# Robo.net
KiCad netlist of a schematic drawn in Altium Designer
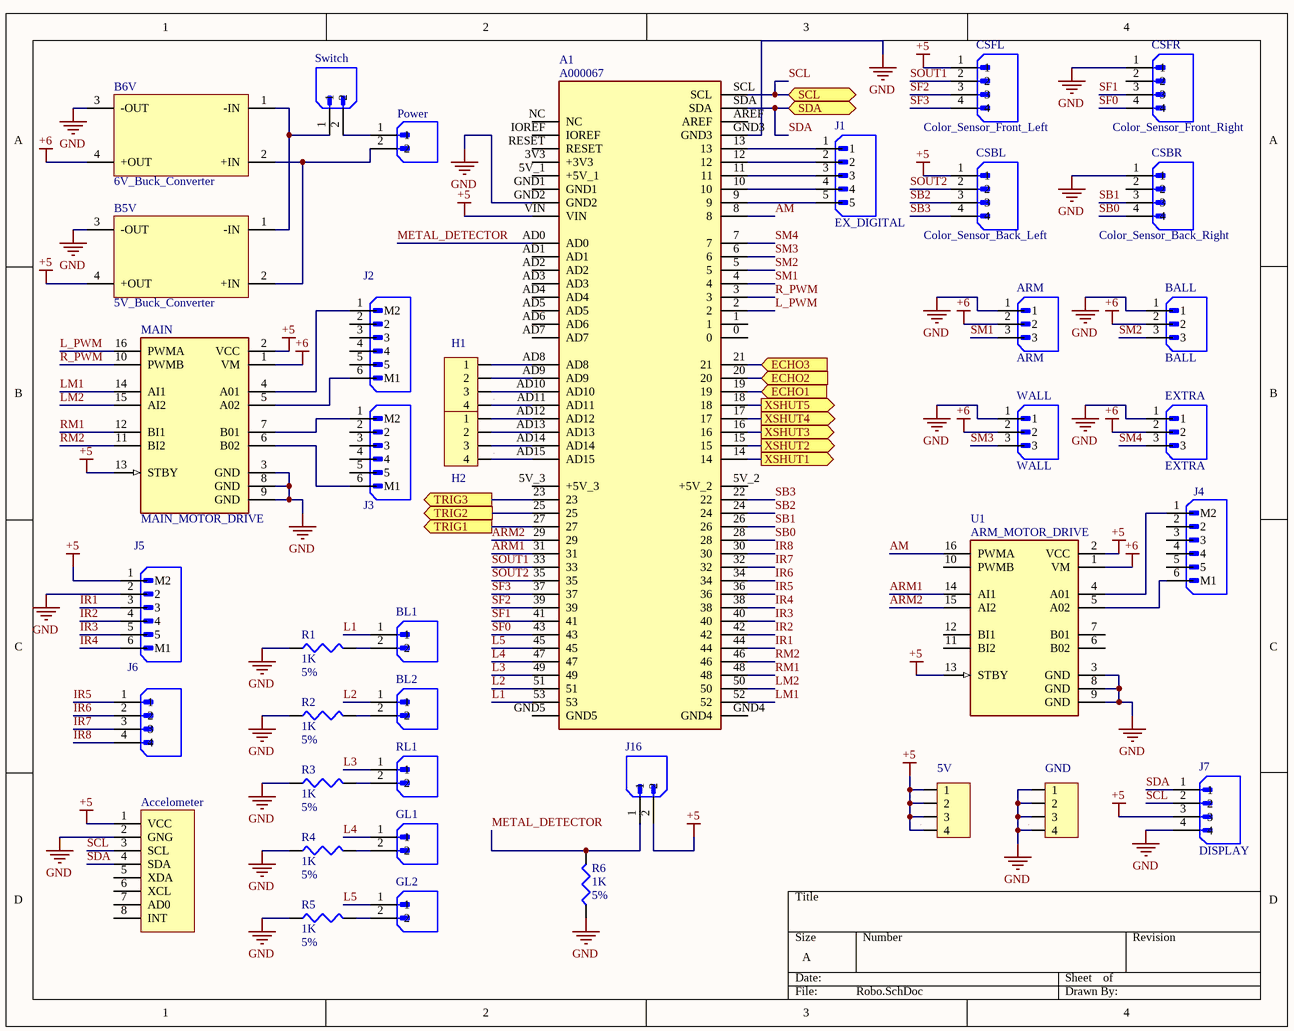
[diagram p0: Robo.SchDoc]

(export (version "E")
  (design (tool "Eeschema 10.0.6"))
  (components
    (comp (ref "5V")
      (value "61300411121")
      (footprint "61300411121 - duplicate - duplicate")
      (fields (field (name "MANUFACTURER") "Wurth Electronics"))
      (libsource (lib "") (part "61300411121_1"))
    )
    (comp (ref "A1")
      (value "A000067")
      (footprint "ARDUINO_A000067")
      (fields (field (name "MF") "Arduino"))
      (libsource (lib "robo") (part "A000067"))
    )
    (comp (ref "Accelometer")
      (value "Accelometer")
      (footprint "8pin_header")
      (libsource (lib "robo") (part "8pin_headers"))
    )
    (comp (ref "ARM")
      (value "ARM")
      (footprint "JST_B3B-XH-A (LF)(SN)")
      (description "Connector Header Through Hole 3 position 0.098 (2.50mm)")
      (fields (field (name "MF") "JST Sales America Inc.") (field (name "MP") "B3B-XH-A (LF)(SN)"))
      (libsource (lib "robo") (part "B3B-XH-A_(LF)(SN)"))
    )
    (comp (ref "B5V")
      (value "5V_Buck_Converter")
      (footprint "Buck_Conveter")
      (libsource (lib "robo") (part "Buck_Converter"))
    )
    (comp (ref "B6V")
      (value "6V_Buck_Converter")
      (footprint "Buck_Conveter")
      (libsource (lib "robo") (part "Buck_Converter"))
    )
    (comp (ref "BALL")
      (value "BALL")
      (footprint "JST_B3B-XH-A (LF)(SN)")
      (description "Connector Header Through Hole 3 position 0.098 (2.50mm)")
      (fields (field (name "MF") "JST Sales America Inc.") (field (name "MP") "B3B-XH-A (LF)(SN)"))
      (libsource (lib "robo") (part "B3B-XH-A_(LF)(SN)"))
    )
    (comp (ref "BL1")
      (value "B2B-XH-A(LF)(SN)")
      (footprint "JST_B2B-XH-A(LF)(SN)")
      (description "Connector Header Through Hole 2 position 0.098 (2.50mm)")
      (fields (field (name "MF") "JST Sales America Inc."))
      (libsource (lib "robo") (part "B2B-XH-A(LF)(SN)"))
    )
    (comp (ref "BL2")
      (value "B2B-XH-A(LF)(SN)")
      (footprint "JST_B2B-XH-A(LF)(SN)")
      (description "Connector Header Through Hole 2 position 0.098 (2.50mm)")
      (fields (field (name "MF") "JST Sales America Inc."))
      (libsource (lib "robo") (part "B2B-XH-A(LF)(SN)"))
    )
    (comp (ref "CSBL")
      (value "Color_Sensor_Back_Left")
      (footprint "JST_B4B-XH-A(LF)(SN)")
      (description "Connector Header Through Hole 4 position 0.098 (2.50mm)")
      (fields (field (name "MP") "B4B-XH-A(LF)(SN)") (field (name "MF") "JST Sales"))
      (libsource (lib "robo") (part "B4B-XH-A(LF)(SN)"))
    )
    (comp (ref "CSBR")
      (value "Color_Sensor_Back_Right")
      (footprint "JST_B4B-XH-A(LF)(SN)")
      (description "Connector Header Through Hole 4 position 0.098 (2.50mm)")
      (fields (field (name "MP") "B4B-XH-A(LF)(SN)") (field (name "MF") "JST Sales"))
      (libsource (lib "robo") (part "B4B-XH-A(LF)(SN)"))
    )
    (comp (ref "CSFL")
      (value "Color_Sensor_Front_Left")
      (footprint "JST_B4B-XH-A(LF)(SN)")
      (description "Connector Header Through Hole 4 position 0.098 (2.50mm)")
      (fields (field (name "MP") "B4B-XH-A(LF)(SN)") (field (name "MF") "JST Sales"))
      (libsource (lib "robo") (part "B4B-XH-A(LF)(SN)"))
    )
    (comp (ref "CSFR")
      (value "Color_Sensor_Front_Right")
      (footprint "JST_B4B-XH-A(LF)(SN)")
      (description "Connector Header Through Hole 4 position 0.098 (2.50mm)")
      (fields (field (name "MP") "B4B-XH-A(LF)(SN)") (field (name "MF") "JST Sales"))
      (libsource (lib "robo") (part "B4B-XH-A(LF)(SN)"))
    )
    (comp (ref "EXTRA")
      (value "EXTRA")
      (footprint "JST_B3B-XH-A (LF)(SN)")
      (description "Connector Header Through Hole 3 position 0.098 (2.50mm)")
      (fields (field (name "MF") "JST Sales America Inc.") (field (name "MP") "B3B-XH-A (LF)(SN)"))
      (libsource (lib "robo") (part "B3B-XH-A_(LF)(SN)"))
    )
    (comp (ref "GL1")
      (value "B2B-XH-A(LF)(SN)")
      (footprint "JST_B2B-XH-A(LF)(SN)")
      (description "Connector Header Through Hole 2 position 0.098 (2.50mm)")
      (fields (field (name "MF") "JST Sales America Inc."))
      (libsource (lib "robo") (part "B2B-XH-A(LF)(SN)"))
    )
    (comp (ref "GL2")
      (value "B2B-XH-A(LF)(SN)")
      (footprint "JST_B2B-XH-A(LF)(SN)")
      (description "Connector Header Through Hole 2 position 0.098 (2.50mm)")
      (fields (field (name "MF") "JST Sales America Inc."))
      (libsource (lib "robo") (part "B2B-XH-A(LF)(SN)"))
    )
    (comp (ref "GND")
      (value "61300411121")
      (footprint "61300411121 - duplicate - duplicate")
      (fields (field (name "MANUFACTURER") "Wurth Electronics"))
      (libsource (lib "") (part "61300411121_1"))
    )
    (comp (ref "H1")
      (value "61300411121")
      (footprint "61300411121 - duplicate - duplicate")
      (fields (field (name "MANUFACTURER") "Wurth Electronics"))
      (libsource (lib "robo") (part "61300411121"))
    )
    (comp (ref "H2")
      (value "61300411121")
      (footprint "61300411121 - duplicate - duplicate")
      (fields (field (name "MANUFACTURER") "Wurth Electronics"))
      (libsource (lib "robo") (part "61300411121"))
    )
    (comp (ref "J1")
      (value "EX_DIGITAL")
      (footprint "JST_B5B-XH-A(LF)(SN)")
      (description "Connector Header Through Hole 5 position 0.098 (2.50mm)")
      (fields (field (name "MF") "JST Sales America Inc.") (field (name "MP") "B5B-XH-A(LF)(SN)"))
      (libsource (lib "robo") (part "B5B-XH-A(LF)(SN)"))
    )
    (comp (ref "J2")
      (value "B6B-XH-A(LF)(SN)")
      (footprint "JST_B6B-XH-A(LF)(SN)")
      (description "Connector Header Through Hole 6 position 0.098 (2.50mm)")
      (fields (field (name "MF") "JST Sales"))
      (libsource (lib "robo") (part "B6B-XH-A(LF)(SN)"))
    )
    (comp (ref "J3")
      (value "B6B-XH-A(LF)(SN)")
      (footprint "JST_B6B-XH-A(LF)(SN)")
      (description "Connector Header Through Hole 6 position 0.098 (2.50mm)")
      (fields (field (name "MF") "JST Sales"))
      (libsource (lib "robo") (part "B6B-XH-A(LF)(SN)"))
    )
    (comp (ref "J4")
      (value "B6B-XH-A(LF)(SN)")
      (footprint "JST_B6B-XH-A(LF)(SN)")
      (description "Connector Header Through Hole 6 position 0.098 (2.50mm)")
      (fields (field (name "MF") "JST Sales"))
      (libsource (lib "robo") (part "B6B-XH-A(LF)(SN)"))
    )
    (comp (ref "J5")
      (value "B6B-XH-A(LF)(SN)")
      (footprint "JST_B6B-XH-A(LF)(SN)")
      (description "Connector Header Through Hole 6 position 0.098 (2.50mm)")
      (fields (field (name "MF") "JST Sales"))
      (libsource (lib "robo") (part "B6B-XH-A(LF)(SN)"))
    )
    (comp (ref "J6")
      (value "B4B-XH-A(LF)(SN)")
      (footprint "JST_B4B-XH-A(LF)(SN)")
      (description "Connector Header Through Hole 4 position 0.098 (2.50mm)")
      (fields (field (name "MF") "JST Sales"))
      (libsource (lib "robo") (part "B4B-XH-A(LF)(SN)"))
    )
    (comp (ref "J7")
      (value "DISPLAY")
      (footprint "JST_B4B-XH-A(LF)(SN)")
      (description "Connector Header Through Hole 4 position 0.098 (2.50mm)")
      (fields (field (name "MP") "B4B-XH-A(LF)(SN)") (field (name "MF") "JST Sales"))
      (libsource (lib "robo") (part "B4B-XH-A(LF)(SN)"))
    )
    (comp (ref "J16")
      (value "B2B-XH-A(LF)(SN)")
      (footprint "JST_B2B-XH-A(LF)(SN)")
      (description "Connector Header Through Hole 2 position 0.098 (2.50mm)")
      (fields (field (name "MF") "JST Sales America Inc."))
      (libsource (lib "") (part "B2B-XH-A(LF)(SN)_1"))
    )
    (comp (ref "MAIN")
      (value "MAIN_MOTOR_DRIVE")
      (footprint "MODULE_ROB-14450")
      (description "TB6612FNG Motor Controller/Driver Power Management Evaluation Board")
      (fields (field (name "MP") "ROB-14450") (field (name "MF") "SparkFun Electronics"))
      (libsource (lib "robo") (part "ROB-14450"))
    )
    (comp (ref "Power")
      (value "B2B-XH-A(LF)(SN)")
      (footprint "JST_B2B-XH-A(LF)(SN)")
      (description "Connector Header Through Hole 2 position 0.098 (2.50mm)")
      (fields (field (name "MF") "JST Sales America Inc."))
      (libsource (lib "robo") (part "B2B-XH-A(LF)(SN)"))
    )
    (comp (ref "R1")
      (value "CFM12JT1K00")
      (footprint "Resister")
      (description "Fixed Resistor, Carbon Film, 0.5W, 1000ohm, 350V, 5% +/-Tol, -400,0ppm/Cel, Through Hole Mount")
      (fields
        (field (name "MANUFACTURER") "Stackpole Electronics")
        (field (name "POWER") "500mW")
        (field (name "RESISTANCE") "1K")
        (field (name "TOLERANCE") "5%")
      )
      (libsource (lib "robo") (part "CFM12JT1K00"))
    )
    (comp (ref "R2")
      (value "CFM12JT1K00")
      (footprint "Resister")
      (description "Fixed Resistor, Carbon Film, 0.5W, 1000ohm, 350V, 5% +/-Tol, -400,0ppm/Cel, Through Hole Mount")
      (fields
        (field (name "MANUFACTURER") "Stackpole Electronics")
        (field (name "POWER") "500mW")
        (field (name "RESISTANCE") "1K")
        (field (name "TOLERANCE") "5%")
      )
      (libsource (lib "robo") (part "CFM12JT1K00"))
    )
    (comp (ref "R3")
      (value "CFM12JT1K00")
      (footprint "Resister")
      (description "Fixed Resistor, Carbon Film, 0.5W, 1000ohm, 350V, 5% +/-Tol, -400,0ppm/Cel, Through Hole Mount")
      (fields
        (field (name "MANUFACTURER") "Stackpole Electronics")
        (field (name "POWER") "500mW")
        (field (name "RESISTANCE") "1K")
        (field (name "TOLERANCE") "5%")
      )
      (libsource (lib "robo") (part "CFM12JT1K00"))
    )
    (comp (ref "R4")
      (value "CFM12JT1K00")
      (footprint "Resister")
      (description "Fixed Resistor, Carbon Film, 0.5W, 1000ohm, 350V, 5% +/-Tol, -400,0ppm/Cel, Through Hole Mount")
      (fields
        (field (name "MANUFACTURER") "Stackpole Electronics")
        (field (name "POWER") "500mW")
        (field (name "RESISTANCE") "1K")
        (field (name "TOLERANCE") "5%")
      )
      (libsource (lib "robo") (part "CFM12JT1K00"))
    )
    (comp (ref "R5")
      (value "CFM12JT1K00")
      (footprint "Resister")
      (description "Fixed Resistor, Carbon Film, 0.5W, 1000ohm, 350V, 5% +/-Tol, -400,0ppm/Cel, Through Hole Mount")
      (fields
        (field (name "MANUFACTURER") "Stackpole Electronics")
        (field (name "POWER") "500mW")
        (field (name "RESISTANCE") "1K")
        (field (name "TOLERANCE") "5%")
      )
      (libsource (lib "robo") (part "CFM12JT1K00"))
    )
    (comp (ref "R6")
      (value "CFM12JT1K00")
      (footprint "Resister")
      (description "Fixed Resistor, Carbon Film, 0.5W, 1000ohm, 350V, 5% +/-Tol, -400,0ppm/Cel, Through Hole Mount")
      (fields
        (field (name "MANUFACTURER") "Stackpole Electronics")
        (field (name "POWER") "500mW")
        (field (name "RESISTANCE") "1K")
        (field (name "TOLERANCE") "5%")
      )
      (libsource (lib "robo") (part "CFM12JT1K00"))
    )
    (comp (ref "RL1")
      (value "B2B-XH-A(LF)(SN)")
      (footprint "JST_B2B-XH-A(LF)(SN)")
      (description "Connector Header Through Hole 2 position 0.098 (2.50mm)")
      (fields (field (name "MF") "JST Sales America Inc."))
      (libsource (lib "robo") (part "B2B-XH-A(LF)(SN)"))
    )
    (comp (ref "Switch")
      (value "B2B-XH-A(LF)(SN)")
      (footprint "JST_B2B-XH-A(LF)(SN)")
      (description "Connector Header Through Hole 2 position 0.098 (2.50mm)")
      (fields (field (name "MF") "JST Sales America Inc."))
      (libsource (lib "") (part "B2B-XH-A(LF)(SN)_1"))
    )
    (comp (ref "U1")
      (value "ARM_MOTOR_DRIVE")
      (footprint "MODULE_ROB-14450")
      (description "TB6612FNG Motor Controller/Driver Power Management Evaluation Board")
      (fields (field (name "MP") "ROB-14450") (field (name "MF") "SparkFun Electronics"))
      (libsource (lib "robo") (part "ROB-14450"))
    )
    (comp (ref "WALL")
      (value "WALL")
      (footprint "JST_B3B-XH-A (LF)(SN)")
      (description "Connector Header Through Hole 3 position 0.098 (2.50mm)")
      (fields (field (name "MF") "JST Sales America Inc.") (field (name "MP") "B3B-XH-A (LF)(SN)"))
      (libsource (lib "robo") (part "B3B-XH-A_(LF)(SN)"))
    )
  )
  (nets
    (net (code "1") (name "+5") (class "Default")
      (node (ref "5V") (pin "1") (pinfunction "1_1") (pintype "passive"))
      (node (ref "5V") (pin "2") (pinfunction "2_2") (pintype "passive"))
      (node (ref "5V") (pin "3") (pinfunction "3_3") (pintype "passive"))
      (node (ref "5V") (pin "4") (pinfunction "4_4") (pintype "passive"))
      (node (ref "A1") (pin "VIN") (pinfunction "VIN_VIN") (pintype "passive"))
      (node (ref "Accelometer") (pin "1") (pinfunction "VCC_1") (pintype "passive"))
      (node (ref "B5V") (pin "4") (pinfunction "+OUT_4") (pintype "passive"))
      (node (ref "CSBL") (pin "1") (pinfunction "1_1") (pintype "passive"))
      (node (ref "CSFL") (pin "1") (pinfunction "1_1") (pintype "passive"))
      (node (ref "J16") (pin "2") (pinfunction "2_2") (pintype "passive"))
      (node (ref "J5") (pin "1") (pinfunction "M2_1") (pintype "passive"))
      (node (ref "J7") (pin "3") (pinfunction "3_3") (pintype "passive"))
      (node (ref "MAIN") (pin "13") (pinfunction "STBY_13") (pintype "input"))
      (node (ref "MAIN") (pin "2") (pinfunction "VCC_2") (pintype "power_in"))
      (node (ref "U1") (pin "13") (pinfunction "STBY_13") (pintype "input"))
      (node (ref "U1") (pin "2") (pinfunction "VCC_2") (pintype "power_in"))
    )
    (net (code "2") (name "+6") (class "Default")
      (node (ref "ARM") (pin "2") (pinfunction "2_2") (pintype "passive"))
      (node (ref "B6V") (pin "4") (pinfunction "+OUT_4") (pintype "passive"))
      (node (ref "BALL") (pin "2") (pinfunction "2_2") (pintype "passive"))
      (node (ref "EXTRA") (pin "2") (pinfunction "2_2") (pintype "passive"))
      (node (ref "MAIN") (pin "1") (pinfunction "VM_1") (pintype "power_in"))
      (node (ref "U1") (pin "1") (pinfunction "VM_1") (pintype "power_in"))
      (node (ref "WALL") (pin "2") (pinfunction "2_2") (pintype "passive"))
    )
    (net (code "3") (name "/AM") (class "Default")
      (node (ref "A1") (pin "8") (pinfunction "8_8") (pintype "passive"))
      (node (ref "U1") (pin "16") (pinfunction "PWMA_16") (pintype "passive"))
    )
    (net (code "4") (name "/ARM1") (class "Default")
      (node (ref "A1") (pin "31") (pinfunction "31_31") (pintype "passive"))
      (node (ref "U1") (pin "14") (pinfunction "AI1_14") (pintype "passive"))
    )
    (net (code "5") (name "/ARM2") (class "Default")
      (node (ref "A1") (pin "29") (pinfunction "29_29") (pintype "passive"))
      (node (ref "U1") (pin "15") (pinfunction "AI2_15") (pintype "passive"))
    )
    (net (code "6") (name "/ECHO1") (class "Default")
      (node (ref "A1") (pin "19") (pinfunction "19_19") (pintype "passive"))
    )
    (net (code "7") (name "/ECHO2") (class "Default")
      (node (ref "A1") (pin "20") (pinfunction "20_20") (pintype "passive"))
    )
    (net (code "8") (name "/ECHO3") (class "Default")
      (node (ref "A1") (pin "21") (pinfunction "21_21") (pintype "passive"))
    )
    (net (code "9") (name "/IR1") (class "Default")
      (node (ref "A1") (pin "44") (pinfunction "44_44") (pintype "passive"))
      (node (ref "J5") (pin "3") (pinfunction "3_3") (pintype "passive"))
    )
    (net (code "10") (name "/IR2") (class "Default")
      (node (ref "A1") (pin "42") (pinfunction "42_42") (pintype "passive"))
      (node (ref "J5") (pin "4") (pinfunction "4_4") (pintype "passive"))
    )
    (net (code "11") (name "/IR3") (class "Default")
      (node (ref "A1") (pin "40") (pinfunction "40_40") (pintype "passive"))
      (node (ref "J5") (pin "5") (pinfunction "5_5") (pintype "passive"))
    )
    (net (code "12") (name "/IR4") (class "Default")
      (node (ref "A1") (pin "38") (pinfunction "38_38") (pintype "passive"))
      (node (ref "J5") (pin "6") (pinfunction "M1_6") (pintype "passive"))
    )
    (net (code "13") (name "/IR5") (class "Default")
      (node (ref "A1") (pin "36") (pinfunction "36_36") (pintype "passive"))
      (node (ref "J6") (pin "1") (pinfunction "1_1") (pintype "passive"))
    )
    (net (code "14") (name "/IR6") (class "Default")
      (node (ref "A1") (pin "34") (pinfunction "34_34") (pintype "passive"))
      (node (ref "J6") (pin "2") (pinfunction "2_2") (pintype "passive"))
    )
    (net (code "15") (name "/IR7") (class "Default")
      (node (ref "A1") (pin "32") (pinfunction "32_32") (pintype "passive"))
      (node (ref "J6") (pin "3") (pinfunction "3_3") (pintype "passive"))
    )
    (net (code "16") (name "/IR8") (class "Default")
      (node (ref "A1") (pin "30") (pinfunction "30_30") (pintype "passive"))
      (node (ref "J6") (pin "4") (pinfunction "4_4") (pintype "passive"))
    )
    (net (code "17") (name "/L1") (class "Default")
      (node (ref "A1") (pin "53") (pinfunction "53_53") (pintype "passive"))
      (node (ref "BL1") (pin "1") (pinfunction "1_1") (pintype "passive"))
    )
    (net (code "18") (name "/L2") (class "Default")
      (node (ref "A1") (pin "51") (pinfunction "51_51") (pintype "passive"))
      (node (ref "BL2") (pin "1") (pinfunction "1_1") (pintype "passive"))
    )
    (net (code "19") (name "/L3") (class "Default")
      (node (ref "A1") (pin "49") (pinfunction "49_49") (pintype "passive"))
      (node (ref "RL1") (pin "1") (pinfunction "1_1") (pintype "passive"))
    )
    (net (code "20") (name "/L4") (class "Default")
      (node (ref "A1") (pin "47") (pinfunction "47_47") (pintype "passive"))
      (node (ref "GL1") (pin "1") (pinfunction "1_1") (pintype "passive"))
    )
    (net (code "21") (name "/L5") (class "Default")
      (node (ref "A1") (pin "45") (pinfunction "45_45") (pintype "passive"))
      (node (ref "GL2") (pin "1") (pinfunction "1_1") (pintype "passive"))
    )
    (net (code "22") (name "/LM1") (class "Default")
      (node (ref "A1") (pin "52") (pinfunction "52_52") (pintype "passive"))
      (node (ref "MAIN") (pin "14") (pinfunction "AI1_14") (pintype "passive"))
    )
    (net (code "23") (name "/LM2") (class "Default")
      (node (ref "A1") (pin "50") (pinfunction "50_50") (pintype "passive"))
      (node (ref "MAIN") (pin "15") (pinfunction "AI2_15") (pintype "passive"))
    )
    (net (code "24") (name "/L_PWM") (class "Default")
      (node (ref "A1") (pin "2") (pinfunction "2_2") (pintype "passive"))
      (node (ref "MAIN") (pin "16") (pinfunction "PWMA_16") (pintype "passive"))
    )
    (net (code "25") (name "/METAL_DETECTOR") (class "Default")
      (node (ref "A1") (pin "AD0") (pinfunction "AD0_AD0") (pintype "passive"))
      (node (ref "J16") (pin "1") (pinfunction "1_1") (pintype "passive"))
      (node (ref "R6") (pin "2") (pinfunction "2_2") (pintype "passive"))
    )
    (net (code "26") (name "/RM1") (class "Default")
      (node (ref "A1") (pin "48") (pinfunction "48_48") (pintype "passive"))
      (node (ref "MAIN") (pin "12") (pinfunction "BI1_12") (pintype "passive"))
    )
    (net (code "27") (name "/RM2") (class "Default")
      (node (ref "A1") (pin "46") (pinfunction "46_46") (pintype "passive"))
      (node (ref "MAIN") (pin "11") (pinfunction "BI2_11") (pintype "passive"))
    )
    (net (code "28") (name "/R_PWM") (class "Default")
      (node (ref "A1") (pin "3") (pinfunction "3_3") (pintype "passive"))
      (node (ref "MAIN") (pin "10") (pinfunction "PWMB_10") (pintype "passive"))
    )
    (net (code "29") (name "/SB0") (class "Default")
      (node (ref "A1") (pin "28") (pinfunction "28_28") (pintype "passive"))
      (node (ref "CSBR") (pin "4") (pinfunction "4_4") (pintype "passive"))
    )
    (net (code "30") (name "/SB1") (class "Default")
      (node (ref "A1") (pin "26") (pinfunction "26_26") (pintype "passive"))
      (node (ref "CSBR") (pin "3") (pinfunction "3_3") (pintype "passive"))
    )
    (net (code "31") (name "/SB2") (class "Default")
      (node (ref "A1") (pin "24") (pinfunction "24_24") (pintype "passive"))
      (node (ref "CSBL") (pin "3") (pinfunction "3_3") (pintype "passive"))
    )
    (net (code "32") (name "/SB3") (class "Default")
      (node (ref "A1") (pin "22") (pinfunction "22_22") (pintype "passive"))
      (node (ref "CSBL") (pin "4") (pinfunction "4_4") (pintype "passive"))
    )
    (net (code "33") (name "/SCL") (class "Default")
      (node (ref "A1") (pin "SCL") (pinfunction "SCL_SCL") (pintype "passive"))
      (node (ref "Accelometer") (pin "3") (pinfunction "SCL_3") (pintype "passive"))
      (node (ref "J7") (pin "2") (pinfunction "2_2") (pintype "passive"))
    )
    (net (code "34") (name "/SDA") (class "Default")
      (node (ref "A1") (pin "SDA") (pinfunction "SDA_SDA") (pintype "passive"))
      (node (ref "Accelometer") (pin "4") (pinfunction "SDA_4") (pintype "passive"))
      (node (ref "J7") (pin "1") (pinfunction "1_1") (pintype "passive"))
    )
    (net (code "35") (name "/SF0") (class "Default")
      (node (ref "A1") (pin "43") (pinfunction "43_43") (pintype "passive"))
      (node (ref "CSFR") (pin "4") (pinfunction "4_4") (pintype "passive"))
    )
    (net (code "36") (name "/SF1") (class "Default")
      (node (ref "A1") (pin "41") (pinfunction "41_41") (pintype "passive"))
      (node (ref "CSFR") (pin "3") (pinfunction "3_3") (pintype "passive"))
    )
    (net (code "37") (name "/SF2") (class "Default")
      (node (ref "A1") (pin "39") (pinfunction "39_39") (pintype "passive"))
      (node (ref "CSFL") (pin "3") (pinfunction "3_3") (pintype "passive"))
    )
    (net (code "38") (name "/SF3") (class "Default")
      (node (ref "A1") (pin "37") (pinfunction "37_37") (pintype "passive"))
      (node (ref "CSFL") (pin "4") (pinfunction "4_4") (pintype "passive"))
    )
    (net (code "39") (name "/SM1") (class "Default")
      (node (ref "A1") (pin "4") (pinfunction "4_4") (pintype "passive"))
      (node (ref "ARM") (pin "3") (pinfunction "3_3") (pintype "passive"))
    )
    (net (code "40") (name "/SM2") (class "Default")
      (node (ref "A1") (pin "5") (pinfunction "5_5") (pintype "passive"))
      (node (ref "BALL") (pin "3") (pinfunction "3_3") (pintype "passive"))
    )
    (net (code "41") (name "/SM3") (class "Default")
      (node (ref "A1") (pin "6") (pinfunction "6_6") (pintype "passive"))
      (node (ref "WALL") (pin "3") (pinfunction "3_3") (pintype "passive"))
    )
    (net (code "42") (name "/SM4") (class "Default")
      (node (ref "A1") (pin "7") (pinfunction "7_7") (pintype "passive"))
      (node (ref "EXTRA") (pin "3") (pinfunction "3_3") (pintype "passive"))
    )
    (net (code "43") (name "/SOUT1") (class "Default")
      (node (ref "A1") (pin "33") (pinfunction "33_33") (pintype "passive"))
      (node (ref "CSFL") (pin "2") (pinfunction "2_2") (pintype "passive"))
    )
    (net (code "44") (name "/SOUT2") (class "Default")
      (node (ref "A1") (pin "35") (pinfunction "35_35") (pintype "passive"))
      (node (ref "CSBL") (pin "2") (pinfunction "2_2") (pintype "passive"))
    )
    (net (code "45") (name "/TRIG1") (class "Default")
      (node (ref "A1") (pin "27") (pinfunction "27_27") (pintype "passive"))
    )
    (net (code "46") (name "/TRIG2") (class "Default")
      (node (ref "A1") (pin "25") (pinfunction "25_25") (pintype "passive"))
    )
    (net (code "47") (name "/TRIG3") (class "Default")
      (node (ref "A1") (pin "23") (pinfunction "23_23") (pintype "passive"))
    )
    (net (code "48") (name "/XSHUT1") (class "Default")
      (node (ref "A1") (pin "14") (pinfunction "14_14") (pintype "passive"))
    )
    (net (code "49") (name "/XSHUT2") (class "Default")
      (node (ref "A1") (pin "15") (pinfunction "15_15") (pintype "passive"))
    )
    (net (code "50") (name "/XSHUT3") (class "Default")
      (node (ref "A1") (pin "16") (pinfunction "16_16") (pintype "passive"))
    )
    (net (code "51") (name "/XSHUT4") (class "Default")
      (node (ref "A1") (pin "17") (pinfunction "17_17") (pintype "passive"))
    )
    (net (code "52") (name "/XSHUT5") (class "Default")
      (node (ref "A1") (pin "18") (pinfunction "18_18") (pintype "passive"))
    )
    (net (code "53") (name "GND") (class "Default")
      (node (ref "A1") (pin "GND2") (pinfunction "GND2_GND2") (pintype "passive"))
      (node (ref "A1") (pin "GND3") (pinfunction "GND3_GND3") (pintype "passive"))
      (node (ref "ARM") (pin "1") (pinfunction "1_1") (pintype "passive"))
      (node (ref "Accelometer") (pin "2") (pinfunction "GNG_2") (pintype "passive"))
      (node (ref "B5V") (pin "3") (pinfunction "-OUT_3") (pintype "passive"))
      (node (ref "B6V") (pin "3") (pinfunction "-OUT_3") (pintype "passive"))
      (node (ref "BALL") (pin "1") (pinfunction "1_1") (pintype "passive"))
      (node (ref "CSBR") (pin "1") (pinfunction "1_1") (pintype "passive"))
      (node (ref "CSFR") (pin "1") (pinfunction "1_1") (pintype "passive"))
      (node (ref "EXTRA") (pin "1") (pinfunction "1_1") (pintype "passive"))
      (node (ref "GND") (pin "1") (pinfunction "1_1") (pintype "passive"))
      (node (ref "GND") (pin "2") (pinfunction "2_2") (pintype "passive"))
      (node (ref "GND") (pin "3") (pinfunction "3_3") (pintype "passive"))
      (node (ref "GND") (pin "4") (pinfunction "4_4") (pintype "passive"))
      (node (ref "J5") (pin "2") (pinfunction "2_2") (pintype "passive"))
      (node (ref "J7") (pin "4") (pinfunction "4_4") (pintype "passive"))
      (node (ref "MAIN") (pin "3") (pinfunction "GND_3") (pintype "power_in"))
      (node (ref "MAIN") (pin "8") (pinfunction "GND_8") (pintype "power_in"))
      (node (ref "MAIN") (pin "9") (pinfunction "GND_9") (pintype "power_in"))
      (node (ref "R1") (pin "1") (pinfunction "1_1") (pintype "passive"))
      (node (ref "R2") (pin "1") (pinfunction "1_1") (pintype "passive"))
      (node (ref "R3") (pin "1") (pinfunction "1_1") (pintype "passive"))
      (node (ref "R4") (pin "1") (pinfunction "1_1") (pintype "passive"))
      (node (ref "R5") (pin "1") (pinfunction "1_1") (pintype "passive"))
      (node (ref "R6") (pin "1") (pinfunction "1_1") (pintype "passive"))
      (node (ref "U1") (pin "3") (pinfunction "GND_3") (pintype "power_in"))
      (node (ref "U1") (pin "8") (pinfunction "GND_8") (pintype "power_in"))
      (node (ref "U1") (pin "9") (pinfunction "GND_9") (pintype "power_in"))
      (node (ref "WALL") (pin "1") (pinfunction "1_1") (pintype "passive"))
    )
    (net (code "54") (name "Net-(A1-Pad9)") (class "Default")
      (node (ref "A1") (pin "9") (pinfunction "9_9") (pintype "passive"))
      (node (ref "J1") (pin "5") (pinfunction "5_5") (pintype "passive"))
    )
    (net (code "55") (name "Net-(A1-Pad10)") (class "Default")
      (node (ref "A1") (pin "10") (pinfunction "10_10") (pintype "passive"))
      (node (ref "J1") (pin "4") (pinfunction "4_4") (pintype "passive"))
    )
    (net (code "56") (name "Net-(A1-Pad11)") (class "Default")
      (node (ref "A1") (pin "11") (pinfunction "11_11") (pintype "passive"))
      (node (ref "J1") (pin "3") (pinfunction "3_3") (pintype "passive"))
    )
    (net (code "57") (name "Net-(A1-Pad12)") (class "Default")
      (node (ref "A1") (pin "12") (pinfunction "12_12") (pintype "passive"))
      (node (ref "J1") (pin "2") (pinfunction "2_2") (pintype "passive"))
    )
    (net (code "58") (name "Net-(A1-Pad13)") (class "Default")
      (node (ref "A1") (pin "13") (pinfunction "13_13") (pintype "passive"))
      (node (ref "J1") (pin "1") (pinfunction "1_1") (pintype "passive"))
    )
    (net (code "59") (name "Net-(A1-PadAD8)") (class "Default")
      (node (ref "A1") (pin "AD8") (pinfunction "AD8_AD8") (pintype "passive"))
      (node (ref "H1") (pin "1") (pinfunction "1_1") (pintype "passive"))
    )
    (net (code "60") (name "Net-(A1-PadAD9)") (class "Default")
      (node (ref "A1") (pin "AD9") (pinfunction "AD9_AD9") (pintype "passive"))
      (node (ref "H1") (pin "2") (pinfunction "2_2") (pintype "passive"))
    )
    (net (code "61") (name "Net-(A1-PadAD10)") (class "Default")
      (node (ref "A1") (pin "AD10") (pinfunction "AD10_AD10") (pintype "passive"))
      (node (ref "H1") (pin "3") (pinfunction "3_3") (pintype "passive"))
    )
    (net (code "62") (name "Net-(A1-PadAD11)") (class "Default")
      (node (ref "A1") (pin "AD11") (pinfunction "AD11_AD11") (pintype "passive"))
      (node (ref "H1") (pin "4") (pinfunction "4_4") (pintype "passive"))
    )
    (net (code "63") (name "Net-(A1-PadAD12)") (class "Default")
      (node (ref "A1") (pin "AD12") (pinfunction "AD12_AD12") (pintype "passive"))
      (node (ref "H2") (pin "1") (pinfunction "1_1") (pintype "passive"))
    )
    (net (code "64") (name "Net-(A1-PadAD13)") (class "Default")
      (node (ref "A1") (pin "AD13") (pinfunction "AD13_AD13") (pintype "passive"))
      (node (ref "H2") (pin "2") (pinfunction "2_2") (pintype "passive"))
    )
    (net (code "65") (name "Net-(A1-PadAD14)") (class "Default")
      (node (ref "A1") (pin "AD14") (pinfunction "AD14_AD14") (pintype "passive"))
      (node (ref "H2") (pin "3") (pinfunction "3_3") (pintype "passive"))
    )
    (net (code "66") (name "Net-(A1-PadAD15)") (class "Default")
      (node (ref "A1") (pin "AD15") (pinfunction "AD15_AD15") (pintype "passive"))
      (node (ref "H2") (pin "4") (pinfunction "4_4") (pintype "passive"))
    )
    (net (code "67") (name "Net-(B5V-+IN)") (class "Default")
      (node (ref "B5V") (pin "2") (pinfunction "+IN_2") (pintype "passive"))
      (node (ref "B6V") (pin "2") (pinfunction "+IN_2") (pintype "passive"))
      (node (ref "Power") (pin "2") (pinfunction "2_2") (pintype "passive"))
    )
    (net (code "68") (name "Net-(B5V--IN)") (class "Default")
      (node (ref "B5V") (pin "1") (pinfunction "-IN_1") (pintype "passive"))
      (node (ref "B6V") (pin "1") (pinfunction "-IN_1") (pintype "passive"))
      (node (ref "Switch") (pin "1") (pinfunction "1_1") (pintype "passive"))
    )
    (net (code "69") (name "Net-(BL1-Pad2)") (class "Default")
      (node (ref "BL1") (pin "2") (pinfunction "2_2") (pintype "passive"))
      (node (ref "R1") (pin "2") (pinfunction "2_2") (pintype "passive"))
    )
    (net (code "70") (name "Net-(BL2-Pad2)") (class "Default")
      (node (ref "BL2") (pin "2") (pinfunction "2_2") (pintype "passive"))
      (node (ref "R2") (pin "2") (pinfunction "2_2") (pintype "passive"))
    )
    (net (code "71") (name "Net-(GL1-Pad2)") (class "Default")
      (node (ref "GL1") (pin "2") (pinfunction "2_2") (pintype "passive"))
      (node (ref "R4") (pin "2") (pinfunction "2_2") (pintype "passive"))
    )
    (net (code "72") (name "Net-(GL2-Pad2)") (class "Default")
      (node (ref "GL2") (pin "2") (pinfunction "2_2") (pintype "passive"))
      (node (ref "R5") (pin "2") (pinfunction "2_2") (pintype "passive"))
    )
    (net (code "73") (name "Net-(J2-M1)") (class "Default")
      (node (ref "J2") (pin "6") (pinfunction "M1_6") (pintype "passive"))
      (node (ref "MAIN") (pin "5") (pinfunction "A02_5") (pintype "passive"))
    )
    (net (code "74") (name "Net-(J2-M2)") (class "Default")
      (node (ref "J2") (pin "1") (pinfunction "M2_1") (pintype "passive"))
      (node (ref "MAIN") (pin "4") (pinfunction "A01_4") (pintype "passive"))
    )
    (net (code "75") (name "Net-(J3-M1)") (class "Default")
      (node (ref "J3") (pin "6") (pinfunction "M1_6") (pintype "passive"))
      (node (ref "MAIN") (pin "6") (pinfunction "B02_6") (pintype "passive"))
    )
    (net (code "76") (name "Net-(J3-M2)") (class "Default")
      (node (ref "J3") (pin "1") (pinfunction "M2_1") (pintype "passive"))
      (node (ref "MAIN") (pin "7") (pinfunction "B01_7") (pintype "passive"))
    )
    (net (code "77") (name "Net-(J4-M1)") (class "Default")
      (node (ref "J4") (pin "6") (pinfunction "M1_6") (pintype "passive"))
      (node (ref "U1") (pin "5") (pinfunction "A02_5") (pintype "passive"))
    )
    (net (code "78") (name "Net-(J4-M2)") (class "Default")
      (node (ref "J4") (pin "1") (pinfunction "M2_1") (pintype "passive"))
      (node (ref "U1") (pin "4") (pinfunction "A01_4") (pintype "passive"))
    )
    (net (code "79") (name "Net-(Power-Pad1)") (class "Default")
      (node (ref "Power") (pin "1") (pinfunction "1_1") (pintype "passive"))
      (node (ref "Switch") (pin "2") (pinfunction "2_2") (pintype "passive"))
    )
    (net (code "80") (name "Net-(R3-Pad2)") (class "Default")
      (node (ref "R3") (pin "2") (pinfunction "2_2") (pintype "passive"))
      (node (ref "RL1") (pin "2") (pinfunction "2_2") (pintype "passive"))
    )
    (net (code "81") (name "unconnected-(A1-+3V3-Pad3V3)") (class "Default")
      (node (ref "A1") (pin "3V3") (pinfunction "+3V3_3V3") (pintype "passive"))
    )
    (net (code "82") (name "unconnected-(A1-+5V_1-Pad5V_1)") (class "Default")
      (node (ref "A1") (pin "5V_1") (pinfunction "+5V_1_5V_1") (pintype "passive"))
    )
    (net (code "83") (name "unconnected-(A1-+5V_2-Pad5V_2)") (class "Default")
      (node (ref "A1") (pin "5V_2") (pinfunction "+5V_2_5V_2") (pintype "passive"))
    )
    (net (code "84") (name "unconnected-(A1-+5V_3-Pad5V_3)") (class "Default")
      (node (ref "A1") (pin "5V_3") (pinfunction "+5V_3_5V_3") (pintype "passive"))
    )
    (net (code "85") (name "unconnected-(A1-Pad0)") (class "Default")
      (node (ref "A1") (pin "0") (pinfunction "0_0") (pintype "passive"))
    )
    (net (code "86") (name "unconnected-(A1-Pad1)") (class "Default")
      (node (ref "A1") (pin "1") (pinfunction "1_1") (pintype "passive"))
    )
    (net (code "87") (name "unconnected-(A1-PadAD1)") (class "Default")
      (node (ref "A1") (pin "AD1") (pinfunction "AD1_AD1") (pintype "passive"))
    )
    (net (code "88") (name "unconnected-(A1-PadAD2)") (class "Default")
      (node (ref "A1") (pin "AD2") (pinfunction "AD2_AD2") (pintype "passive"))
    )
    (net (code "89") (name "unconnected-(A1-PadAD3)") (class "Default")
      (node (ref "A1") (pin "AD3") (pinfunction "AD3_AD3") (pintype "passive"))
    )
    (net (code "90") (name "unconnected-(A1-PadAD4)") (class "Default")
      (node (ref "A1") (pin "AD4") (pinfunction "AD4_AD4") (pintype "passive"))
    )
    (net (code "91") (name "unconnected-(A1-PadAD5)") (class "Default")
      (node (ref "A1") (pin "AD5") (pinfunction "AD5_AD5") (pintype "passive"))
    )
    (net (code "92") (name "unconnected-(A1-PadAD6)") (class "Default")
      (node (ref "A1") (pin "AD6") (pinfunction "AD6_AD6") (pintype "passive"))
    )
    (net (code "93") (name "unconnected-(A1-PadAD7)") (class "Default")
      (node (ref "A1") (pin "AD7") (pinfunction "AD7_AD7") (pintype "passive"))
    )
    (net (code "94") (name "unconnected-(A1-PadAREF)") (class "Default")
      (node (ref "A1") (pin "AREF") (pinfunction "AREF_AREF") (pintype "passive"))
    )
    (net (code "95") (name "unconnected-(A1-PadGND1)") (class "Default")
      (node (ref "A1") (pin "GND1") (pinfunction "GND1_GND1") (pintype "passive"))
    )
    (net (code "96") (name "unconnected-(A1-PadGND4)") (class "Default")
      (node (ref "A1") (pin "GND4") (pinfunction "GND4_GND4") (pintype "passive"))
    )
    (net (code "97") (name "unconnected-(A1-PadGND5)") (class "Default")
      (node (ref "A1") (pin "GND5") (pinfunction "GND5_GND5") (pintype "passive"))
    )
    (net (code "98") (name "unconnected-(A1-PadIOREF)") (class "Default")
      (node (ref "A1") (pin "IOREF") (pinfunction "IOREF_IOREF") (pintype "passive"))
    )
    (net (code "99") (name "unconnected-(A1-PadNC)") (class "Default")
      (node (ref "A1") (pin "NC") (pinfunction "NC_NC") (pintype "passive"))
    )
    (net (code "100") (name "unconnected-(A1-PadRESET)") (class "Default")
      (node (ref "A1") (pin "RESET") (pinfunction "RESET_RESET") (pintype "passive"))
    )
    (net (code "101") (name "unconnected-(Accelometer-AD0-Pad7)") (class "Default")
      (node (ref "Accelometer") (pin "7") (pinfunction "AD0_7") (pintype "passive"))
    )
    (net (code "102") (name "unconnected-(Accelometer-INT-Pad8)") (class "Default")
      (node (ref "Accelometer") (pin "8") (pinfunction "INT_8") (pintype "passive"))
    )
    (net (code "103") (name "unconnected-(Accelometer-XCL-Pad6)") (class "Default")
      (node (ref "Accelometer") (pin "6") (pinfunction "XCL_6") (pintype "passive"))
    )
    (net (code "104") (name "unconnected-(Accelometer-XDA-Pad5)") (class "Default")
      (node (ref "Accelometer") (pin "5") (pinfunction "XDA_5") (pintype "passive"))
    )
    (net (code "105") (name "unconnected-(CSBR-Pad2)") (class "Default")
      (node (ref "CSBR") (pin "2") (pinfunction "2_2") (pintype "passive"))
    )
    (net (code "106") (name "unconnected-(CSFR-Pad2)") (class "Default")
      (node (ref "CSFR") (pin "2") (pinfunction "2_2") (pintype "passive"))
    )
    (net (code "107") (name "unconnected-(J2-Pad2)") (class "Default")
      (node (ref "J2") (pin "2") (pinfunction "2_2") (pintype "passive"))
    )
    (net (code "108") (name "unconnected-(J2-Pad3)") (class "Default")
      (node (ref "J2") (pin "3") (pinfunction "3_3") (pintype "passive"))
    )
    (net (code "109") (name "unconnected-(J2-Pad4)") (class "Default")
      (node (ref "J2") (pin "4") (pinfunction "4_4") (pintype "passive"))
    )
    (net (code "110") (name "unconnected-(J2-Pad5)") (class "Default")
      (node (ref "J2") (pin "5") (pinfunction "5_5") (pintype "passive"))
    )
    (net (code "111") (name "unconnected-(J3-Pad2)") (class "Default")
      (node (ref "J3") (pin "2") (pinfunction "2_2") (pintype "passive"))
    )
    (net (code "112") (name "unconnected-(J3-Pad3)") (class "Default")
      (node (ref "J3") (pin "3") (pinfunction "3_3") (pintype "passive"))
    )
    (net (code "113") (name "unconnected-(J3-Pad4)") (class "Default")
      (node (ref "J3") (pin "4") (pinfunction "4_4") (pintype "passive"))
    )
    (net (code "114") (name "unconnected-(J3-Pad5)") (class "Default")
      (node (ref "J3") (pin "5") (pinfunction "5_5") (pintype "passive"))
    )
    (net (code "115") (name "unconnected-(J4-Pad2)") (class "Default")
      (node (ref "J4") (pin "2") (pinfunction "2_2") (pintype "passive"))
    )
    (net (code "116") (name "unconnected-(J4-Pad3)") (class "Default")
      (node (ref "J4") (pin "3") (pinfunction "3_3") (pintype "passive"))
    )
    (net (code "117") (name "unconnected-(J4-Pad4)") (class "Default")
      (node (ref "J4") (pin "4") (pinfunction "4_4") (pintype "passive"))
    )
    (net (code "118") (name "unconnected-(J4-Pad5)") (class "Default")
      (node (ref "J4") (pin "5") (pinfunction "5_5") (pintype "passive"))
    )
    (net (code "119") (name "unconnected-(U1-B01-Pad7)") (class "Default")
      (node (ref "U1") (pin "7") (pinfunction "B01_7") (pintype "passive"))
    )
    (net (code "120") (name "unconnected-(U1-B02-Pad6)") (class "Default")
      (node (ref "U1") (pin "6") (pinfunction "B02_6") (pintype "passive"))
    )
    (net (code "121") (name "unconnected-(U1-BI1-Pad12)") (class "Default")
      (node (ref "U1") (pin "12") (pinfunction "BI1_12") (pintype "passive"))
    )
    (net (code "122") (name "unconnected-(U1-BI2-Pad11)") (class "Default")
      (node (ref "U1") (pin "11") (pinfunction "BI2_11") (pintype "passive"))
    )
    (net (code "123") (name "unconnected-(U1-PWMB-Pad10)") (class "Default")
      (node (ref "U1") (pin "10") (pinfunction "PWMB_10") (pintype "passive"))
    )
  )
)
